# proj_arhipov_mcu.net
KiCad netlist of a schematic drawn in Altium Designer
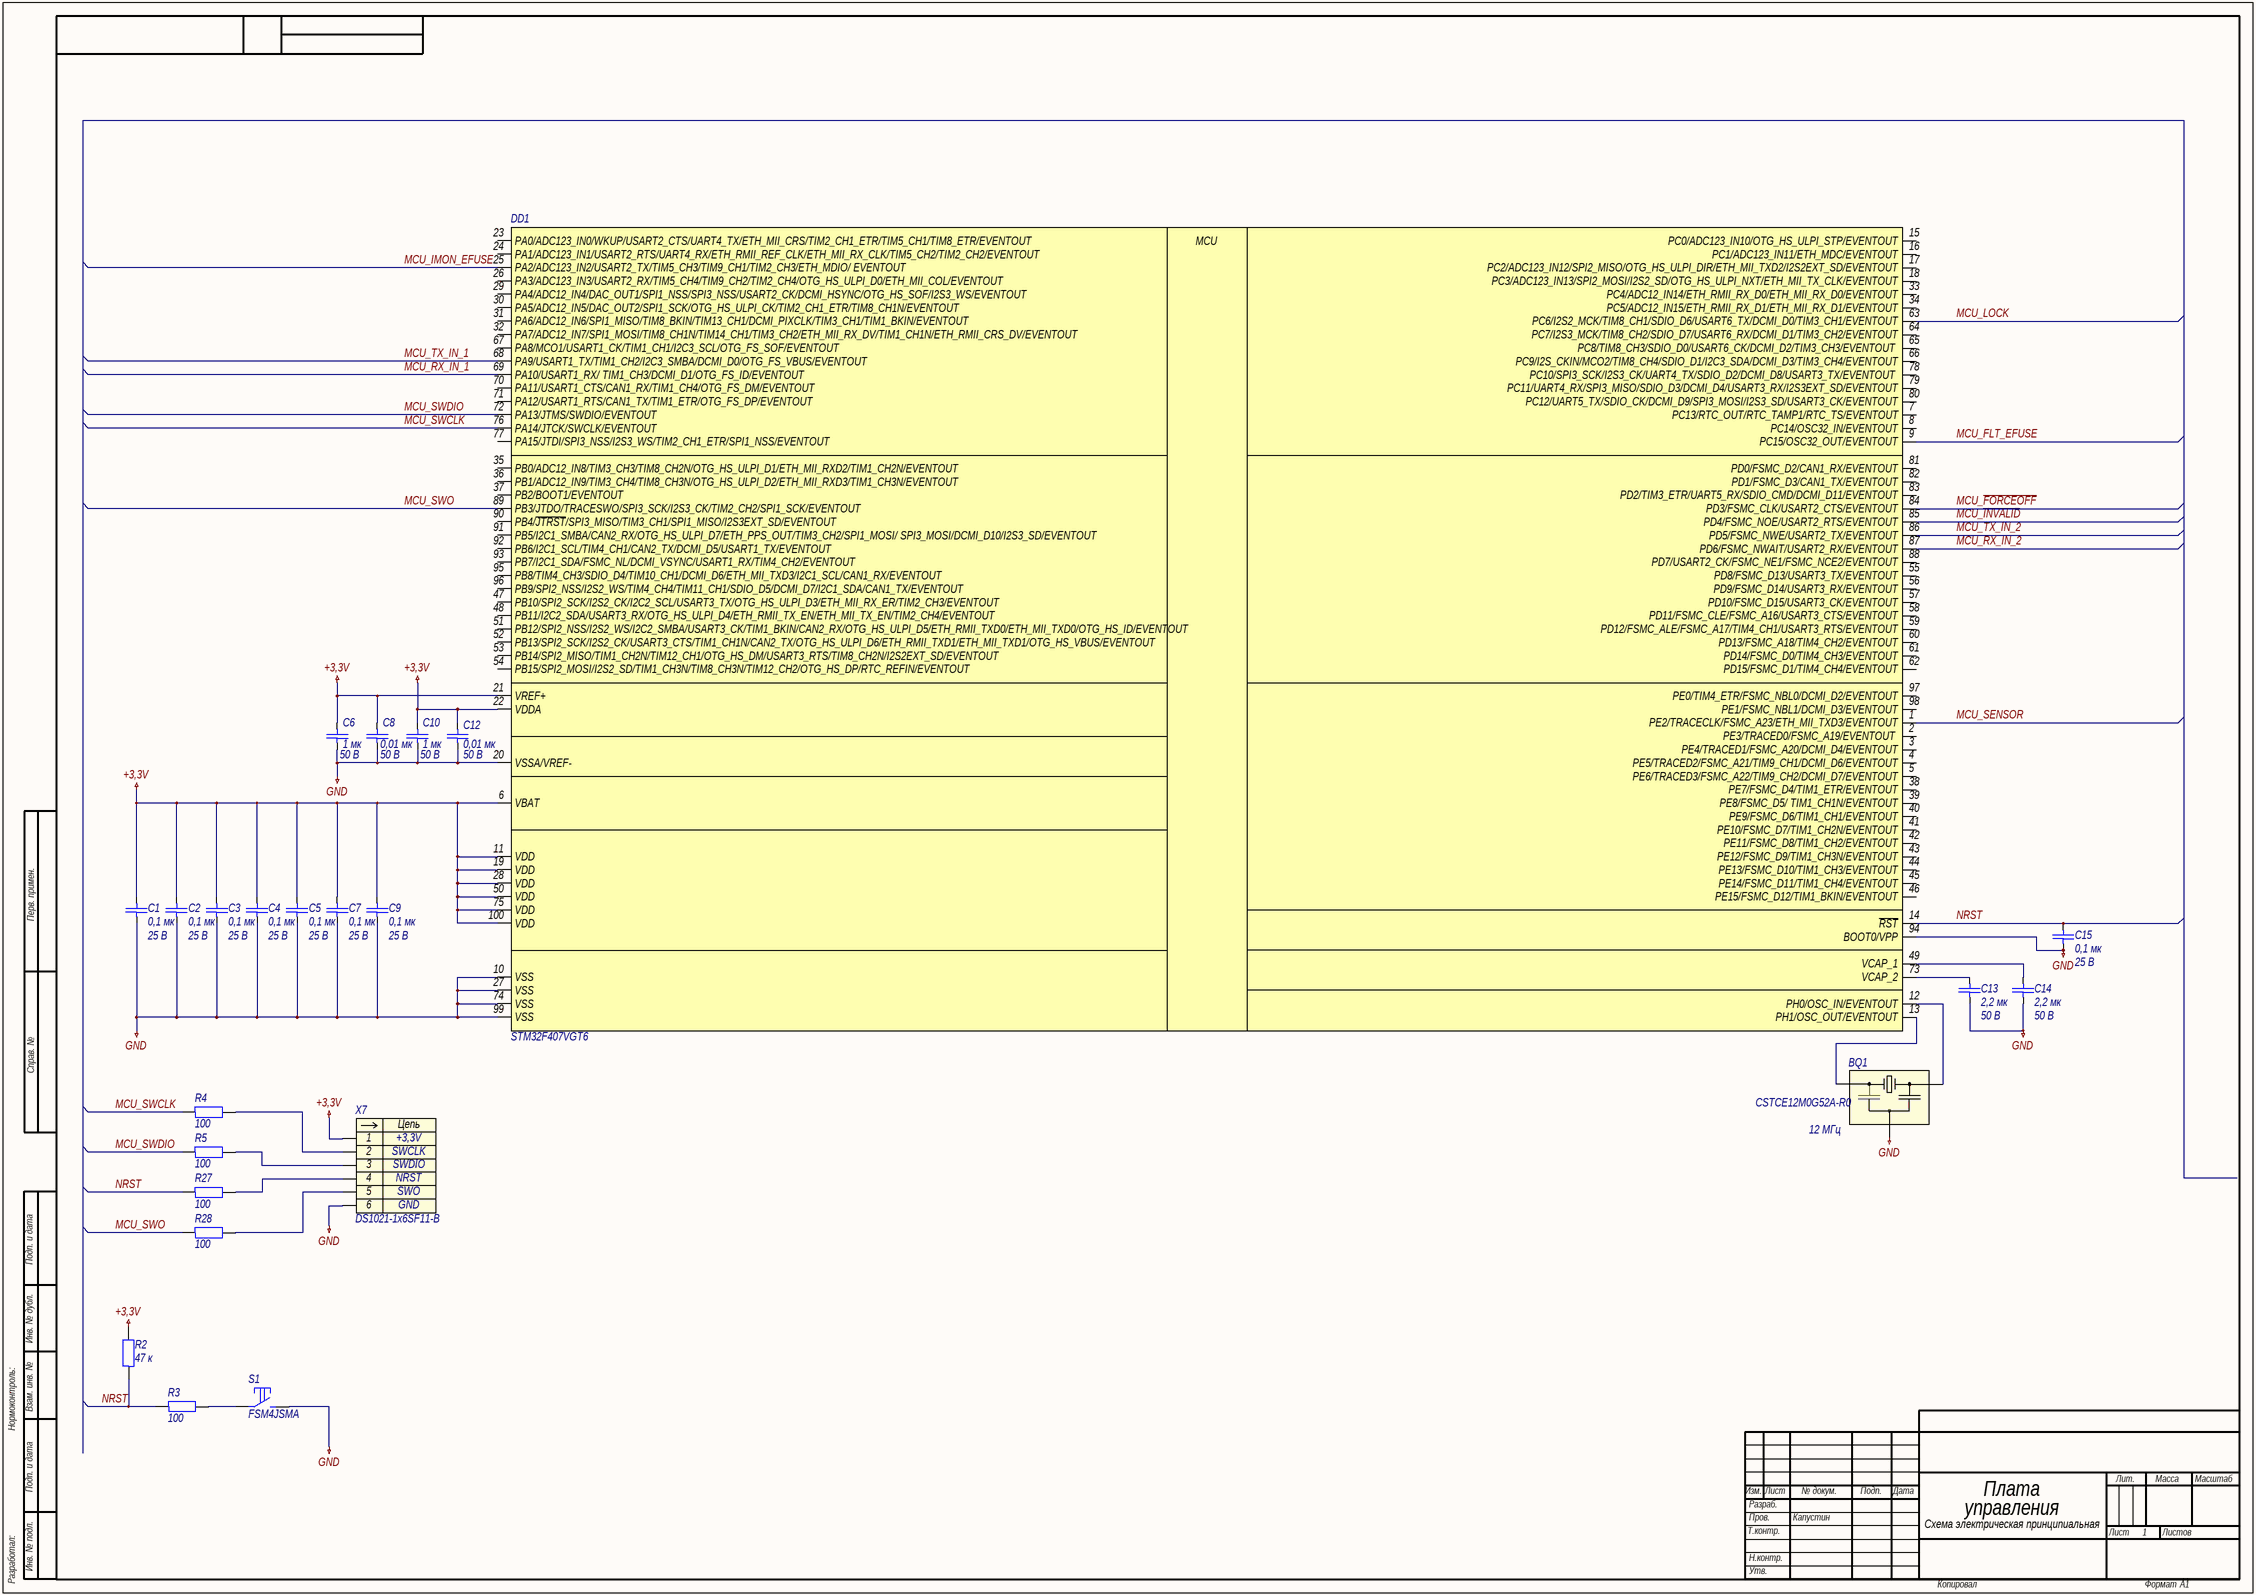
[diagram p0: proj_arhipov_mcu.SchDoc]

(export (version "E")
  (design (tool "Eeschema 10.0.6"))
  (components
    (comp (ref "BQ1")
      (value "CSTCE12M0G52A-R0")
      (footprint "CSTCE-3-320X130X70")
      (description "=Описание")
      (fields (field (name "ЧАСТОТA") "12 МГц"))
      (libsource (lib "Database_Students") (part "CSTCE12M0G52A-R0"))
    )
    (comp (ref "C1")
      (value "0,1 мк")
      (footprint "C0603")
      (description "=Описание")
      (fields (field (name "НАПРЯЖЕНИЕ") "25 В"))
      (libsource (lib "Database_Students") (part "CAPACITOR-NONPOLAR"))
    )
    (comp (ref "C2")
      (value "0,1 мк")
      (footprint "C0603")
      (description "=Описание")
      (fields (field (name "НАПРЯЖЕНИЕ") "25 В"))
      (libsource (lib "Database_Students") (part "CAPACITOR-NONPOLAR"))
    )
    (comp (ref "C3")
      (value "0,1 мк")
      (footprint "C0603")
      (description "=Описание")
      (fields (field (name "НАПРЯЖЕНИЕ") "25 В"))
      (libsource (lib "Database_Students") (part "CAPACITOR-NONPOLAR"))
    )
    (comp (ref "C4")
      (value "0,1 мк")
      (footprint "C0603")
      (description "=Описание")
      (fields (field (name "НАПРЯЖЕНИЕ") "25 В"))
      (libsource (lib "Database_Students") (part "CAPACITOR-NONPOLAR"))
    )
    (comp (ref "C5")
      (value "0,1 мк")
      (footprint "C0603")
      (description "=Описание")
      (fields (field (name "НАПРЯЖЕНИЕ") "25 В"))
      (libsource (lib "Database_Students") (part "CAPACITOR-NONPOLAR"))
    )
    (comp (ref "C6")
      (value "1 мк")
      (footprint "C0603")
      (description "=Описание")
      (fields (field (name "НАПРЯЖЕНИЕ") "50 В"))
      (libsource (lib "Database_Students") (part "CAPACITOR-NONPOLAR"))
    )
    (comp (ref "C7")
      (value "0,1 мк")
      (footprint "C0603")
      (description "=Описание")
      (fields (field (name "НАПРЯЖЕНИЕ") "25 В"))
      (libsource (lib "Database_Students") (part "CAPACITOR-NONPOLAR"))
    )
    (comp (ref "C8")
      (value "0,01 мк")
      (footprint "C0603")
      (description "=Описание")
      (fields (field (name "НАПРЯЖЕНИЕ") "50 В"))
      (libsource (lib "Database_Students") (part "CAPACITOR-NONPOLAR"))
    )
    (comp (ref "C9")
      (value "0,1 мк")
      (footprint "C0603")
      (description "=Описание")
      (fields (field (name "НАПРЯЖЕНИЕ") "25 В"))
      (libsource (lib "Database_Students") (part "CAPACITOR-NONPOLAR"))
    )
    (comp (ref "C10")
      (value "1 мк")
      (footprint "C0603")
      (description "=Описание")
      (fields (field (name "НАПРЯЖЕНИЕ") "50 В"))
      (libsource (lib "Database_Students") (part "CAPACITOR-NONPOLAR"))
    )
    (comp (ref "C12")
      (value "0,01 мк")
      (footprint "C0603")
      (description "=Описание")
      (fields (field (name "НАПРЯЖЕНИЕ") "50 В"))
      (libsource (lib "Database_Students") (part "CAPACITOR-NONPOLAR"))
    )
    (comp (ref "C13")
      (value "2,2 мк")
      (footprint "C0603")
      (description "=Описание")
      (fields (field (name "НАПРЯЖЕНИЕ") "50 В"))
      (libsource (lib "Database_Students") (part "CAPACITOR-NONPOLAR"))
    )
    (comp (ref "C14")
      (value "2,2 мк")
      (footprint "C0603")
      (description "=Описание")
      (fields (field (name "НАПРЯЖЕНИЕ") "50 В"))
      (libsource (lib "Database_Students") (part "CAPACITOR-NONPOLAR"))
    )
    (comp (ref "C15")
      (value "0,1 мк")
      (footprint "C0603")
      (description "=Описание")
      (fields (field (name "НАПРЯЖЕНИЕ") "25 В"))
      (libsource (lib "Database_Students") (part "CAPACITOR-NONPOLAR"))
    )
    (comp (ref "DD1")
      (value "STM32F407VGT6")
      (footprint "LQFP-100-P50-1400X1400X160-L60X22")
      (description "=Описание")
      (libsource (lib "Database_Students") (part "STM32F407VGT6"))
    )
    (comp (ref "R2")
      (value "47 к")
      (footprint "R0603")
      (description "=Описание")
      (libsource (lib "Database_Students") (part "RESISTOR-COMMON"))
    )
    (comp (ref "R3")
      (value "100")
      (footprint "R0603")
      (description "=Описание")
      (libsource (lib "Database_Students") (part "RESISTOR-COMMON"))
    )
    (comp (ref "R4")
      (value "100")
      (footprint "R0603")
      (description "=Описание")
      (libsource (lib "Database_Students") (part "RESISTOR-COMMON"))
    )
    (comp (ref "R5")
      (value "100")
      (footprint "R0603")
      (description "=Описание")
      (libsource (lib "Database_Students") (part "RESISTOR-COMMON"))
    )
    (comp (ref "R27")
      (value "100")
      (footprint "R0603")
      (description "=Описание")
      (libsource (lib "Database_Students") (part "RESISTOR-COMMON"))
    )
    (comp (ref "R28")
      (value "100")
      (footprint "R0603")
      (description "=Описание")
      (libsource (lib "Database_Students") (part "RESISTOR-COMMON"))
    )
    (comp (ref "S1")
      (value "FSM4JSMA")
      (footprint "FSM4JSMA")
      (description "=Описание")
      (libsource (lib "Database_Students") (part "BUTTON"))
    )
    (comp (ref "X7")
      (value "DS1021-1x6SF11-B")
      (footprint "DS1021-1X6SF11-B")
      (description "=Описание")
      (libsource (lib "Database_Students") (part "HEADER-6-PLG"))
    )
  )
  (nets
    (net (code "1") (name "+3,3V") (class "Default")
      (node (ref "C1") (pin "1") (pinfunction "1_1") (pintype "passive"))
      (node (ref "C10") (pin "1") (pinfunction "1_1") (pintype "passive"))
      (node (ref "C12") (pin "1") (pinfunction "1_1") (pintype "passive"))
      (node (ref "C2") (pin "1") (pinfunction "1_1") (pintype "passive"))
      (node (ref "C3") (pin "1") (pinfunction "1_1") (pintype "passive"))
      (node (ref "C4") (pin "1") (pinfunction "1_1") (pintype "passive"))
      (node (ref "C5") (pin "1") (pinfunction "1_1") (pintype "passive"))
      (node (ref "C6") (pin "1") (pinfunction "1_1") (pintype "passive"))
      (node (ref "C7") (pin "1") (pinfunction "1_1") (pintype "passive"))
      (node (ref "C8") (pin "1") (pinfunction "1_1") (pintype "passive"))
      (node (ref "C9") (pin "1") (pinfunction "1_1") (pintype "passive"))
      (node (ref "DD1") (pin "100") (pinfunction "VDD_100") (pintype "passive"))
      (node (ref "DD1") (pin "11") (pinfunction "VDD_11") (pintype "passive"))
      (node (ref "DD1") (pin "19") (pinfunction "VDD_19") (pintype "passive"))
      (node (ref "DD1") (pin "21") (pinfunction "VREF+_21") (pintype "passive"))
      (node (ref "DD1") (pin "22") (pinfunction "VDDA_22") (pintype "passive"))
      (node (ref "DD1") (pin "28") (pinfunction "VDD_28") (pintype "passive"))
      (node (ref "DD1") (pin "50") (pinfunction "VDD_50") (pintype "passive"))
      (node (ref "DD1") (pin "6") (pinfunction "VBAT_6") (pintype "passive"))
      (node (ref "DD1") (pin "75") (pinfunction "VDD_75") (pintype "passive"))
      (node (ref "R2") (pin "2") (pinfunction "2_2") (pintype "passive"))
      (node (ref "X7") (pin "1") (pinfunction "1_1") (pintype "passive"))
    )
    (net (code "2") (name "/MCU_FLT_EFUSE") (class "Default")
      (node (ref "DD1") (pin "9") (pinfunction "PC15/OSC32_OUT/EVENTOUT_9") (pintype "passive"))
    )
    (net (code "3") (name "/MCU_IMON_EFUSE") (class "Default")
      (node (ref "DD1") (pin "25") (pinfunction "PA2/ADC123_IN2/USART2_TX/TIM5_CH3/TIM9_CH1/TIM2_CH3/ETH_MDIO/_EVENTOUT_25") (pintype "passive"))
    )
    (net (code "4") (name "/MCU_LOCK") (class "Default")
      (node (ref "DD1") (pin "63") (pinfunction "PC6/I2S2_MCK/TIM8_CH1/SDIO_D6/USART6_TX/DCMI_D0/TIM3_CH1/EVENTOUT_63") (pintype "passive"))
    )
    (net (code "5") (name "/MCU_RX_IN_1") (class "Default")
      (node (ref "DD1") (pin "69") (pinfunction "PA10/USART1_RX/_TIM1_CH3/DCMI_D1/OTG_FS_ID/EVENTOUT_69") (pintype "passive"))
    )
    (net (code "6") (name "/MCU_RX_IN_2") (class "Default")
      (node (ref "DD1") (pin "87") (pinfunction "PD6/FSMC_NWAIT/USART2_RX/EVENTOUT_87") (pintype "passive"))
    )
    (net (code "7") (name "/MCU_SENSOR") (class "Default")
      (node (ref "DD1") (pin "1") (pinfunction "PE2/TRACECLK/FSMC_A23/ETH_MII_TXD3/EVENTOUT_1") (pintype "passive"))
    )
    (net (code "8") (name "/MCU_SWCLK") (class "Default")
      (node (ref "DD1") (pin "76") (pinfunction "PA14/JTCK/SWCLK/EVENTOUT_76") (pintype "passive"))
      (node (ref "R4") (pin "1") (pinfunction "1_1") (pintype "passive"))
    )
    (net (code "9") (name "/MCU_SWDIO") (class "Default")
      (node (ref "DD1") (pin "72") (pinfunction "PA13/JTMS/SWDIO/EVENTOUT_72") (pintype "passive"))
      (node (ref "R5") (pin "1") (pinfunction "1_1") (pintype "passive"))
    )
    (net (code "10") (name "/MCU_SWO") (class "Default")
      (node (ref "DD1") (pin "89") (pinfunction "PB3/JTDO/TRACESWO/SPI3_SCK/I2S3_CK/TIM2_CH2/SPI1_SCK/EVENTOUT_89") (pintype "passive"))
      (node (ref "R28") (pin "1") (pinfunction "1_1") (pintype "passive"))
    )
    (net (code "11") (name "/MCU_TX_IN_1") (class "Default")
      (node (ref "DD1") (pin "68") (pinfunction "PA9/USART1_TX/TIM1_CH2/I2C3_SMBA/DCMI_D0/OTG_FS_VBUS/EVENTOUT_68") (pintype "passive"))
    )
    (net (code "12") (name "/MCU_TX_IN_2") (class "Default")
      (node (ref "DD1") (pin "86") (pinfunction "PD5/FSMC_NWE/USART2_TX/EVENTOUT_86") (pintype "passive"))
    )
    (net (code "13") (name "/MCU_~{FORCEOFF}") (class "Default")
      (node (ref "DD1") (pin "84") (pinfunction "PD3/FSMC_CLK/USART2_CTS/EVENTOUT_84") (pintype "passive"))
    )
    (net (code "14") (name "/MCU_~{INVALID}") (class "Default")
      (node (ref "DD1") (pin "85") (pinfunction "PD4/FSMC_NOE/USART2_RTS/EVENTOUT_85") (pintype "passive"))
    )
    (net (code "15") (name "/NRST") (class "Default")
      (node (ref "C15") (pin "1") (pinfunction "1_1") (pintype "passive"))
      (node (ref "DD1") (pin "14") (pinfunction "~{RST}_14") (pintype "passive"))
      (node (ref "R2") (pin "1") (pinfunction "1_1") (pintype "passive"))
      (node (ref "R27") (pin "1") (pinfunction "1_1") (pintype "passive"))
      (node (ref "R3") (pin "1") (pinfunction "1_1") (pintype "passive"))
    )
    (net (code "16") (name "GND") (class "Default")
      (node (ref "BQ1") (pin "2") (pinfunction "2_2") (pintype "passive"))
      (node (ref "C1") (pin "2") (pinfunction "2_2") (pintype "passive"))
      (node (ref "C10") (pin "2") (pinfunction "2_2") (pintype "passive"))
      (node (ref "C12") (pin "2") (pinfunction "2_2") (pintype "passive"))
      (node (ref "C13") (pin "2") (pinfunction "2_2") (pintype "passive"))
      (node (ref "C14") (pin "2") (pinfunction "2_2") (pintype "passive"))
      (node (ref "C15") (pin "2") (pinfunction "2_2") (pintype "passive"))
      (node (ref "C2") (pin "2") (pinfunction "2_2") (pintype "passive"))
      (node (ref "C3") (pin "2") (pinfunction "2_2") (pintype "passive"))
      (node (ref "C4") (pin "2") (pinfunction "2_2") (pintype "passive"))
      (node (ref "C5") (pin "2") (pinfunction "2_2") (pintype "passive"))
      (node (ref "C6") (pin "2") (pinfunction "2_2") (pintype "passive"))
      (node (ref "C7") (pin "2") (pinfunction "2_2") (pintype "passive"))
      (node (ref "C8") (pin "2") (pinfunction "2_2") (pintype "passive"))
      (node (ref "C9") (pin "2") (pinfunction "2_2") (pintype "passive"))
      (node (ref "DD1") (pin "10") (pinfunction "VSS_10") (pintype "passive"))
      (node (ref "DD1") (pin "20") (pinfunction "VSSA/VREF-_20") (pintype "passive"))
      (node (ref "DD1") (pin "27") (pinfunction "VSS_27") (pintype "passive"))
      (node (ref "DD1") (pin "74") (pinfunction "VSS_74") (pintype "passive"))
      (node (ref "DD1") (pin "94") (pinfunction "BOOT0/VPP_94") (pintype "passive"))
      (node (ref "DD1") (pin "99") (pinfunction "VSS_99") (pintype "passive"))
      (node (ref "S1") (pin "2") (pinfunction "2_2") (pintype "passive"))
      (node (ref "X7") (pin "6") (pinfunction "6_6") (pintype "passive"))
    )
    (net (code "17") (name "Net-(DD1-PH0{slash}OSC_IN{slash}EVENTOUT)") (class "Default")
      (node (ref "BQ1") (pin "1") (pinfunction "1_1") (pintype "passive"))
      (node (ref "DD1") (pin "12") (pinfunction "PH0/OSC_IN/EVENTOUT_12") (pintype "passive"))
    )
    (net (code "18") (name "Net-(DD1-PH1{slash}OSC_OUT{slash}EVENTOUT)") (class "Default")
      (node (ref "BQ1") (pin "3") (pinfunction "3_3") (pintype "passive"))
      (node (ref "DD1") (pin "13") (pinfunction "PH1/OSC_OUT/EVENTOUT_13") (pintype "passive"))
    )
    (net (code "19") (name "Net-(DD1-VCAP_1)") (class "Default")
      (node (ref "C14") (pin "1") (pinfunction "1_1") (pintype "passive"))
      (node (ref "DD1") (pin "49") (pinfunction "VCAP_1_49") (pintype "passive"))
    )
    (net (code "20") (name "Net-(DD1-VCAP_2)") (class "Default")
      (node (ref "C13") (pin "1") (pinfunction "1_1") (pintype "passive"))
      (node (ref "DD1") (pin "73") (pinfunction "VCAP_2_73") (pintype "passive"))
    )
    (net (code "21") (name "Net-(R3-Pad2)") (class "Default")
      (node (ref "R3") (pin "2") (pinfunction "2_2") (pintype "passive"))
      (node (ref "S1") (pin "1") (pinfunction "1_1") (pintype "passive"))
    )
    (net (code "22") (name "Net-(R4-Pad2)") (class "Default")
      (node (ref "R4") (pin "2") (pinfunction "2_2") (pintype "passive"))
      (node (ref "X7") (pin "2") (pinfunction "2_2") (pintype "passive"))
    )
    (net (code "23") (name "Net-(R5-Pad2)") (class "Default")
      (node (ref "R5") (pin "2") (pinfunction "2_2") (pintype "passive"))
      (node (ref "X7") (pin "3") (pinfunction "3_3") (pintype "passive"))
    )
    (net (code "24") (name "Net-(R27-Pad2)") (class "Default")
      (node (ref "R27") (pin "2") (pinfunction "2_2") (pintype "passive"))
      (node (ref "X7") (pin "4") (pinfunction "4_4") (pintype "passive"))
    )
    (net (code "25") (name "Net-(R28-Pad2)") (class "Default")
      (node (ref "R28") (pin "2") (pinfunction "2_2") (pintype "passive"))
      (node (ref "X7") (pin "5") (pinfunction "5_5") (pintype "passive"))
    )
    (net (code "26") (name "unconnected-(DD1-PA0{slash}ADC123_IN0{slash}WKUP{slash}USART2_CTS{slash}UART4_TX{slash}ETH_MII_CRS{slash}TIM2_CH1_ETR{slash}TIM5_CH1{slash}TIM8_ETR{slash}EVENTOUT-Pad23)") (class "Default")
      (node (ref "DD1") (pin "23") (pinfunction "PA0/ADC123_IN0/WKUP/USART2_CTS/UART4_TX/ETH_MII_CRS/TIM2_CH1_ETR/TIM5_CH1/TIM8_ETR/EVENTOUT_23") (pintype "passive"))
    )
    (net (code "27") (name "unconnected-(DD1-PA1{slash}ADC123_IN1{slash}USART2_RTS{slash}UART4_RX{slash}ETH_RMII_REF_CLK{slash}ETH_MII_RX_CLK{slash}TIM5_CH2{slash}TIM2_CH2{slash}EVENTOUT-Pad24)") (class "Default")
      (node (ref "DD1") (pin "24") (pinfunction "PA1/ADC123_IN1/USART2_RTS/UART4_RX/ETH_RMII_REF_CLK/ETH_MII_RX_CLK/TIM5_CH2/TIM2_CH2/EVENTOUT_24") (pintype "passive"))
    )
    (net (code "28") (name "unconnected-(DD1-PA3{slash}ADC123_IN3{slash}USART2_RX{slash}TIM5_CH4{slash}TIM9_CH2{slash}TIM2_CH4{slash}OTG_HS_ULPI_D0{slash}ETH_MII_COL{slash}EVENTOUT-Pad26)") (class "Default")
      (node (ref "DD1") (pin "26") (pinfunction "PA3/ADC123_IN3/USART2_RX/TIM5_CH4/TIM9_CH2/TIM2_CH4/OTG_HS_ULPI_D0/ETH_MII_COL/EVENTOUT_26") (pintype "passive"))
    )
    (net (code "29") (name "unconnected-(DD1-PA4{slash}ADC12_IN4{slash}DAC_OUT1{slash}SPI1_NSS{slash}SPI3_NSS{slash}USART2_CK{slash}DCMI_HSYNC{slash}OTG_HS_SOF{slash}I2S3_WS{slash}EVENTOUT-Pad29)") (class "Default")
      (node (ref "DD1") (pin "29") (pinfunction "PA4/ADC12_IN4/DAC_OUT1/SPI1_NSS/SPI3_NSS/USART2_CK/DCMI_HSYNC/OTG_HS_SOF/I2S3_WS/EVENTOUT_29") (pintype "passive"))
    )
    (net (code "30") (name "unconnected-(DD1-PA5{slash}ADC12_IN5{slash}DAC_OUT2{slash}SPI1_SCK{slash}OTG_HS_ULPI_CK{slash}TIM2_CH1_ETR{slash}TIM8_CH1N{slash}EVENTOUT-Pad30)") (class "Default")
      (node (ref "DD1") (pin "30") (pinfunction "PA5/ADC12_IN5/DAC_OUT2/SPI1_SCK/OTG_HS_ULPI_CK/TIM2_CH1_ETR/TIM8_CH1N/EVENTOUT_30") (pintype "passive"))
    )
    (net (code "31") (name "unconnected-(DD1-PA6{slash}ADC12_IN6{slash}SPI1_MISO{slash}TIM8_BKIN{slash}TIM13_CH1{slash}DCMI_PIXCLK{slash}TIM3_CH1{slash}TIM1_BKIN{slash}EVENTOUT-Pad31)") (class "Default")
      (node (ref "DD1") (pin "31") (pinfunction "PA6/ADC12_IN6/SPI1_MISO/TIM8_BKIN/TIM13_CH1/DCMI_PIXCLK/TIM3_CH1/TIM1_BKIN/EVENTOUT_31") (pintype "passive"))
    )
    (net (code "32") (name "unconnected-(DD1-PA7{slash}ADC12_IN7{slash}SPI1_MOSI{slash}TIM8_CH1N{slash}TIM14_CH1{slash}TIM3_CH2{slash}ETH_MII_RX_DV{slash}TIM1_CH1N{slash}ETH_RMII_CRS_DV{slash}EVENTOUT-Pad32)") (class "Default")
      (node (ref "DD1") (pin "32") (pinfunction "PA7/ADC12_IN7/SPI1_MOSI/TIM8_CH1N/TIM14_CH1/TIM3_CH2/ETH_MII_RX_DV/TIM1_CH1N/ETH_RMII_CRS_DV/EVENTOUT_32") (pintype "passive"))
    )
    (net (code "33") (name "unconnected-(DD1-PA8{slash}MCO1{slash}USART1_CK{slash}TIM1_CH1{slash}I2C3_SCL{slash}OTG_FS_SOF{slash}EVENTOUT-Pad67)") (class "Default")
      (node (ref "DD1") (pin "67") (pinfunction "PA8/MCO1/USART1_CK/TIM1_CH1/I2C3_SCL/OTG_FS_SOF/EVENTOUT_67") (pintype "passive"))
    )
    (net (code "34") (name "unconnected-(DD1-PA11{slash}USART1_CTS{slash}CAN1_RX{slash}TIM1_CH4{slash}OTG_FS_DM{slash}EVENTOUT-Pad70)") (class "Default")
      (node (ref "DD1") (pin "70") (pinfunction "PA11/USART1_CTS/CAN1_RX/TIM1_CH4/OTG_FS_DM/EVENTOUT_70") (pintype "passive"))
    )
    (net (code "35") (name "unconnected-(DD1-PA12{slash}USART1_RTS{slash}CAN1_TX{slash}TIM1_ETR{slash}OTG_FS_DP{slash}EVENTOUT-Pad71)") (class "Default")
      (node (ref "DD1") (pin "71") (pinfunction "PA12/USART1_RTS/CAN1_TX/TIM1_ETR/OTG_FS_DP/EVENTOUT_71") (pintype "passive"))
    )
    (net (code "36") (name "unconnected-(DD1-PA15{slash}JTDI{slash}SPI3_NSS{slash}I2S3_WS{slash}TIM2_CH1_ETR{slash}SPI1_NSS{slash}EVENTOUT-Pad77)") (class "Default")
      (node (ref "DD1") (pin "77") (pinfunction "PA15/JTDI/SPI3_NSS/I2S3_WS/TIM2_CH1_ETR/SPI1_NSS/EVENTOUT_77") (pintype "passive"))
    )
    (net (code "37") (name "unconnected-(DD1-PB0{slash}ADC12_IN8{slash}TIM3_CH3{slash}TIM8_CH2N{slash}OTG_HS_ULPI_D1{slash}ETH_MII_RXD2{slash}TIM1_CH2N{slash}EVENTOUT-Pad35)") (class "Default")
      (node (ref "DD1") (pin "35") (pinfunction "PB0/ADC12_IN8/TIM3_CH3/TIM8_CH2N/OTG_HS_ULPI_D1/ETH_MII_RXD2/TIM1_CH2N/EVENTOUT_35") (pintype "passive"))
    )
    (net (code "38") (name "unconnected-(DD1-PB1{slash}ADC12_IN9{slash}TIM3_CH4{slash}TIM8_CH3N{slash}OTG_HS_ULPI_D2{slash}ETH_MII_RXD3{slash}TIM1_CH3N{slash}EVENTOUT-Pad36)") (class "Default")
      (node (ref "DD1") (pin "36") (pinfunction "PB1/ADC12_IN9/TIM3_CH4/TIM8_CH3N/OTG_HS_ULPI_D2/ETH_MII_RXD3/TIM1_CH3N/EVENTOUT_36") (pintype "passive"))
    )
    (net (code "39") (name "unconnected-(DD1-PB2{slash}BOOT1{slash}EVENTOUT-Pad37)") (class "Default")
      (node (ref "DD1") (pin "37") (pinfunction "PB2/BOOT1/EVENTOUT_37") (pintype "passive"))
    )
    (net (code "40") (name "unconnected-(DD1-PB4{slash}~{JTRST}{slash}SPI3_MISO{slash}TIM3_CH1{slash}SPI1_MISO{slash}I2S3EXT_SD{slash}EVENTOUT-Pad90)") (class "Default")
      (node (ref "DD1") (pin "90") (pinfunction "PB4/~{JTRST}/SPI3_MISO/TIM3_CH1/SPI1_MISO/I2S3EXT_SD/EVENTOUT_90") (pintype "passive"))
    )
    (net (code "41") (name "unconnected-(DD1-PB5{slash}I2C1_SMBA{slash}CAN2_RX{slash}OTG_HS_ULPI_D7{slash}ETH_PPS_OUT{slash}TIM3_CH2{slash}SPI1_MOSI{slash}_SPI3_MOSI{slash}DCMI_D10{slash}I2S3_SD{slash}EVENTOUT-Pad91)") (class "Default")
      (node (ref "DD1") (pin "91") (pinfunction "PB5/I2C1_SMBA/CAN2_RX/OTG_HS_ULPI_D7/ETH_PPS_OUT/TIM3_CH2/SPI1_MOSI/_SPI3_MOSI/DCMI_D10/I2S3_SD/EVENTOUT_91") (pintype "passive"))
    )
    (net (code "42") (name "unconnected-(DD1-PB6{slash}I2C1_SCL{slash}TIM4_CH1{slash}CAN2_TX{slash}DCMI_D5{slash}USART1_TX{slash}EVENTOUT-Pad92)") (class "Default")
      (node (ref "DD1") (pin "92") (pinfunction "PB6/I2C1_SCL/TIM4_CH1/CAN2_TX/DCMI_D5/USART1_TX/EVENTOUT_92") (pintype "passive"))
    )
    (net (code "43") (name "unconnected-(DD1-PB7{slash}I2C1_SDA{slash}FSMC_NL{slash}DCMI_VSYNC{slash}USART1_RX{slash}TIM4_CH2{slash}EVENTOUT-Pad93)") (class "Default")
      (node (ref "DD1") (pin "93") (pinfunction "PB7/I2C1_SDA/FSMC_NL/DCMI_VSYNC/USART1_RX/TIM4_CH2/EVENTOUT_93") (pintype "passive"))
    )
    (net (code "44") (name "unconnected-(DD1-PB8{slash}TIM4_CH3{slash}SDIO_D4{slash}TIM10_CH1{slash}DCMI_D6{slash}ETH_MII_TXD3{slash}I2C1_SCL{slash}CAN1_RX{slash}EVENTOUT-Pad95)") (class "Default")
      (node (ref "DD1") (pin "95") (pinfunction "PB8/TIM4_CH3/SDIO_D4/TIM10_CH1/DCMI_D6/ETH_MII_TXD3/I2C1_SCL/CAN1_RX/EVENTOUT_95") (pintype "passive"))
    )
    (net (code "45") (name "unconnected-(DD1-PB9{slash}SPI2_NSS{slash}I2S2_WS{slash}TIM4_CH4{slash}TIM11_CH1{slash}SDIO_D5{slash}DCMI_D7{slash}I2C1_SDA{slash}CAN1_TX{slash}EVENTOUT-Pad96)") (class "Default")
      (node (ref "DD1") (pin "96") (pinfunction "PB9/SPI2_NSS/I2S2_WS/TIM4_CH4/TIM11_CH1/SDIO_D5/DCMI_D7/I2C1_SDA/CAN1_TX/EVENTOUT_96") (pintype "passive"))
    )
    (net (code "46") (name "unconnected-(DD1-PB10{slash}SPI2_SCK{slash}I2S2_CK{slash}I2C2_SCL{slash}USART3_TX{slash}OTG_HS_ULPI_D3{slash}ETH_MII_RX_ER{slash}TIM2_CH3{slash}EVENTOUT-Pad47)") (class "Default")
      (node (ref "DD1") (pin "47") (pinfunction "PB10/SPI2_SCK/I2S2_CK/I2C2_SCL/USART3_TX/OTG_HS_ULPI_D3/ETH_MII_RX_ER/TIM2_CH3/EVENTOUT_47") (pintype "passive"))
    )
    (net (code "47") (name "unconnected-(DD1-PB11{slash}I2C2_SDA{slash}USART3_RX{slash}OTG_HS_ULPI_D4{slash}ETH_RMII_TX_EN{slash}ETH_MII_TX_EN{slash}TIM2_CH4{slash}EVENTOUT-Pad48)") (class "Default")
      (node (ref "DD1") (pin "48") (pinfunction "PB11/I2C2_SDA/USART3_RX/OTG_HS_ULPI_D4/ETH_RMII_TX_EN/ETH_MII_TX_EN/TIM2_CH4/EVENTOUT_48") (pintype "passive"))
    )
    (net (code "48") (name "unconnected-(DD1-PB12{slash}SPI2_NSS{slash}I2S2_WS{slash}I2C2_SMBA{slash}USART3_CK{slash}TIM1_BKIN{slash}CAN2_RX{slash}OTG_HS_ULPI_D5{slash}ETH_RMII_TXD0{slash}ETH_MII_TXD0{slash}OTG_HS_ID{slash}EVENTOUT-Pad51)") (class "Default")
      (node (ref "DD1") (pin "51") (pinfunction "PB12/SPI2_NSS/I2S2_WS/I2C2_SMBA/USART3_CK/TIM1_BKIN/CAN2_RX/OTG_HS_ULPI_D5/ETH_RMII_TXD0/ETH_MII_TXD0/OTG_HS_ID/EVENTOUT_51") (pintype "passive"))
    )
    (net (code "49") (name "unconnected-(DD1-PB13{slash}SPI2_SCK{slash}I2S2_CK{slash}USART3_CTS{slash}TIM1_CH1N{slash}CAN2_TX{slash}OTG_HS_ULPI_D6{slash}ETH_RMII_TXD1{slash}ETH_MII_TXD1{slash}OTG_HS_VBUS{slash}EVENTOUT-Pad52)") (class "Default")
      (node (ref "DD1") (pin "52") (pinfunction "PB13/SPI2_SCK/I2S2_CK/USART3_CTS/TIM1_CH1N/CAN2_TX/OTG_HS_ULPI_D6/ETH_RMII_TXD1/ETH_MII_TXD1/OTG_HS_VBUS/EVENTOUT_52") (pintype "passive"))
    )
    (net (code "50") (name "unconnected-(DD1-PB14{slash}SPI2_MISO{slash}TIM1_CH2N{slash}TIM12_CH1{slash}OTG_HS_DM{slash}USART3_RTS{slash}TIM8_CH2N{slash}I2S2EXT_SD{slash}EVENTOUT-Pad53)") (class "Default")
      (node (ref "DD1") (pin "53") (pinfunction "PB14/SPI2_MISO/TIM1_CH2N/TIM12_CH1/OTG_HS_DM/USART3_RTS/TIM8_CH2N/I2S2EXT_SD/EVENTOUT_53") (pintype "passive"))
    )
    (net (code "51") (name "unconnected-(DD1-PB15{slash}SPI2_MOSI{slash}I2S2_SD{slash}TIM1_CH3N{slash}TIM8_CH3N{slash}TIM12_CH2{slash}OTG_HS_DP{slash}RTC_REFIN{slash}EVENTOUT-Pad54)") (class "Default")
      (node (ref "DD1") (pin "54") (pinfunction "PB15/SPI2_MOSI/I2S2_SD/TIM1_CH3N/TIM8_CH3N/TIM12_CH2/OTG_HS_DP/RTC_REFIN/EVENTOUT_54") (pintype "passive"))
    )
    (net (code "52") (name "unconnected-(DD1-PC0{slash}ADC123_IN10{slash}OTG_HS_ULPI_STP{slash}EVENTOUT-Pad15)") (class "Default")
      (node (ref "DD1") (pin "15") (pinfunction "PC0/ADC123_IN10/OTG_HS_ULPI_STP/EVENTOUT_15") (pintype "passive"))
    )
    (net (code "53") (name "unconnected-(DD1-PC1{slash}ADC123_IN11{slash}ETH_MDC{slash}EVENTOUT-Pad16)") (class "Default")
      (node (ref "DD1") (pin "16") (pinfunction "PC1/ADC123_IN11/ETH_MDC/EVENTOUT_16") (pintype "passive"))
    )
    (net (code "54") (name "unconnected-(DD1-PC2{slash}ADC123_IN12{slash}SPI2_MISO{slash}OTG_HS_ULPI_DIR{slash}ETH_MII_TXD2{slash}I2S2EXT_SD{slash}EVENTOUT-Pad17)") (class "Default")
      (node (ref "DD1") (pin "17") (pinfunction "PC2/ADC123_IN12/SPI2_MISO/OTG_HS_ULPI_DIR/ETH_MII_TXD2/I2S2EXT_SD/EVENTOUT_17") (pintype "passive"))
    )
    (net (code "55") (name "unconnected-(DD1-PC3{slash}ADC123_IN13{slash}SPI2_MOSI{slash}I2S2_SD{slash}OTG_HS_ULPI_NXT{slash}ETH_MII_TX_CLK{slash}EVENTOUT-Pad18)") (class "Default")
      (node (ref "DD1") (pin "18") (pinfunction "PC3/ADC123_IN13/SPI2_MOSI/I2S2_SD/OTG_HS_ULPI_NXT/ETH_MII_TX_CLK/EVENTOUT_18") (pintype "passive"))
    )
    (net (code "56") (name "unconnected-(DD1-PC4{slash}ADC12_IN14{slash}ETH_RMII_RX_D0{slash}ETH_MII_RX_D0{slash}EVENTOUT-Pad33)") (class "Default")
      (node (ref "DD1") (pin "33") (pinfunction "PC4/ADC12_IN14/ETH_RMII_RX_D0/ETH_MII_RX_D0/EVENTOUT_33") (pintype "passive"))
    )
    (net (code "57") (name "unconnected-(DD1-PC5{slash}ADC12_IN15{slash}ETH_RMII_RX_D1{slash}ETH_MII_RX_D1{slash}EVENTOUT-Pad34)") (class "Default")
      (node (ref "DD1") (pin "34") (pinfunction "PC5/ADC12_IN15/ETH_RMII_RX_D1/ETH_MII_RX_D1/EVENTOUT_34") (pintype "passive"))
    )
    (net (code "58") (name "unconnected-(DD1-PC7{slash}I2S3_MCK{slash}TIM8_CH2{slash}SDIO_D7{slash}USART6_RX{slash}DCMI_D1{slash}TIM3_CH2{slash}EVENTOUT-Pad64)") (class "Default")
      (node (ref "DD1") (pin "64") (pinfunction "PC7/I2S3_MCK/TIM8_CH2/SDIO_D7/USART6_RX/DCMI_D1/TIM3_CH2/EVENTOUT_64") (pintype "passive"))
    )
    (net (code "59") (name "unconnected-(DD1-PC8{slash}TIM8_CH3{slash}SDIO_D0{slash}USART6_CK{slash}DCMI_D2{slash}TIM3_CH3{slash}EVENTOUT-Pad65)") (class "Default")
      (node (ref "DD1") (pin "65") (pinfunction "PC8/TIM8_CH3/SDIO_D0/USART6_CK/DCMI_D2/TIM3_CH3/EVENTOUT_65") (pintype "passive"))
    )
    (net (code "60") (name "unconnected-(DD1-PC9{slash}I2S_CKIN{slash}MCO2{slash}TIM8_CH4{slash}SDIO_D1{slash}I2C3_SDA{slash}DCMI_D3{slash}TIM3_CH4{slash}EVENTOUT-Pad66)") (class "Default")
      (node (ref "DD1") (pin "66") (pinfunction "PC9/I2S_CKIN/MCO2/TIM8_CH4/SDIO_D1/I2C3_SDA/DCMI_D3/TIM3_CH4/EVENTOUT_66") (pintype "passive"))
    )
    (net (code "61") (name "unconnected-(DD1-PC10{slash}SPI3_SCK{slash}I2S3_CK{slash}UART4_TX{slash}SDIO_D2{slash}DCMI_D8{slash}USART3_TX{slash}EVENTOUT-Pad78)") (class "Default")
      (node (ref "DD1") (pin "78") (pinfunction "PC10/SPI3_SCK/I2S3_CK/UART4_TX/SDIO_D2/DCMI_D8/USART3_TX/EVENTOUT_78") (pintype "passive"))
    )
    (net (code "62") (name "unconnected-(DD1-PC11{slash}UART4_RX{slash}SPI3_MISO{slash}SDIO_D3{slash}DCMI_D4{slash}USART3_RX{slash}I2S3EXT_SD{slash}EVENTOUT-Pad79)") (class "Default")
      (node (ref "DD1") (pin "79") (pinfunction "PC11/UART4_RX/SPI3_MISO/SDIO_D3/DCMI_D4/USART3_RX/I2S3EXT_SD/EVENTOUT_79") (pintype "passive"))
    )
    (net (code "63") (name "unconnected-(DD1-PC12{slash}UART5_TX{slash}SDIO_CK{slash}DCMI_D9{slash}SPI3_MOSI{slash}I2S3_SD{slash}USART3_CK{slash}EVENTOUT-Pad80)") (class "Default")
      (node (ref "DD1") (pin "80") (pinfunction "PC12/UART5_TX/SDIO_CK/DCMI_D9/SPI3_MOSI/I2S3_SD/USART3_CK/EVENTOUT_80") (pintype "passive"))
    )
    (net (code "64") (name "unconnected-(DD1-PC13{slash}RTC_OUT{slash}RTC_TAMP1{slash}RTC_TS{slash}EVENTOUT-Pad7)") (class "Default")
      (node (ref "DD1") (pin "7") (pinfunction "PC13/RTC_OUT/RTC_TAMP1/RTC_TS/EVENTOUT_7") (pintype "passive"))
    )
    (net (code "65") (name "unconnected-(DD1-PC14{slash}OSC32_IN{slash}EVENTOUT-Pad8)") (class "Default")
      (node (ref "DD1") (pin "8") (pinfunction "PC14/OSC32_IN/EVENTOUT_8") (pintype "passive"))
    )
    (net (code "66") (name "unconnected-(DD1-PD0{slash}FSMC_D2{slash}CAN1_RX{slash}EVENTOUT-Pad81)") (class "Default")
      (node (ref "DD1") (pin "81") (pinfunction "PD0/FSMC_D2/CAN1_RX/EVENTOUT_81") (pintype "passive"))
    )
    (net (code "67") (name "unconnected-(DD1-PD1{slash}FSMC_D3{slash}CAN1_TX{slash}EVENTOUT-Pad82)") (class "Default")
      (node (ref "DD1") (pin "82") (pinfunction "PD1/FSMC_D3/CAN1_TX/EVENTOUT_82") (pintype "passive"))
    )
    (net (code "68") (name "unconnected-(DD1-PD2{slash}TIM3_ETR{slash}UART5_RX{slash}SDIO_CMD{slash}DCMI_D11{slash}EVENTOUT-Pad83)") (class "Default")
      (node (ref "DD1") (pin "83") (pinfunction "PD2/TIM3_ETR/UART5_RX/SDIO_CMD/DCMI_D11/EVENTOUT_83") (pintype "passive"))
    )
    (net (code "69") (name "unconnected-(DD1-PD7{slash}USART2_CK{slash}FSMC_NE1{slash}FSMC_NCE2{slash}EVENTOUT-Pad88)") (class "Default")
      (node (ref "DD1") (pin "88") (pinfunction "PD7/USART2_CK/FSMC_NE1/FSMC_NCE2/EVENTOUT_88") (pintype "passive"))
    )
    (net (code "70") (name "unconnected-(DD1-PD8{slash}FSMC_D13{slash}USART3_TX{slash}EVENTOUT-Pad55)") (class "Default")
      (node (ref "DD1") (pin "55") (pinfunction "PD8/FSMC_D13/USART3_TX/EVENTOUT_55") (pintype "passive"))
    )
    (net (code "71") (name "unconnected-(DD1-PD9{slash}FSMC_D14{slash}USART3_RX{slash}EVENTOUT-Pad56)") (class "Default")
      (node (ref "DD1") (pin "56") (pinfunction "PD9/FSMC_D14/USART3_RX/EVENTOUT_56") (pintype "passive"))
    )
    (net (code "72") (name "unconnected-(DD1-PD10{slash}FSMC_D15{slash}USART3_CK{slash}EVENTOUT-Pad57)") (class "Default")
      (node (ref "DD1") (pin "57") (pinfunction "PD10/FSMC_D15/USART3_CK/EVENTOUT_57") (pintype "passive"))
    )
    (net (code "73") (name "unconnected-(DD1-PD11{slash}FSMC_CLE{slash}FSMC_A16{slash}USART3_CTS{slash}EVENTOUT-Pad58)") (class "Default")
      (node (ref "DD1") (pin "58") (pinfunction "PD11/FSMC_CLE/FSMC_A16/USART3_CTS/EVENTOUT_58") (pintype "passive"))
    )
    (net (code "74") (name "unconnected-(DD1-PD12{slash}FSMC_ALE{slash}FSMC_A17{slash}TIM4_CH1{slash}USART3_RTS{slash}EVENTOUT-Pad59)") (class "Default")
      (node (ref "DD1") (pin "59") (pinfunction "PD12/FSMC_ALE/FSMC_A17/TIM4_CH1/USART3_RTS/EVENTOUT_59") (pintype "passive"))
    )
    (net (code "75") (name "unconnected-(DD1-PD13{slash}FSMC_A18{slash}TIM4_CH2{slash}EVENTOUT-Pad60)") (class "Default")
      (node (ref "DD1") (pin "60") (pinfunction "PD13/FSMC_A18/TIM4_CH2/EVENTOUT_60") (pintype "passive"))
    )
    (net (code "76") (name "unconnected-(DD1-PD14{slash}FSMC_D0{slash}TIM4_CH3{slash}EVENTOUT-Pad61)") (class "Default")
      (node (ref "DD1") (pin "61") (pinfunction "PD14/FSMC_D0/TIM4_CH3/EVENTOUT_61") (pintype "passive"))
    )
    (net (code "77") (name "unconnected-(DD1-PD15{slash}FSMC_D1{slash}TIM4_CH4{slash}EVENTOUT-Pad62)") (class "Default")
      (node (ref "DD1") (pin "62") (pinfunction "PD15/FSMC_D1/TIM4_CH4/EVENTOUT_62") (pintype "passive"))
    )
    (net (code "78") (name "unconnected-(DD1-PE0{slash}TIM4_ETR{slash}FSMC_NBL0{slash}DCMI_D2{slash}EVENTOUT-Pad97)") (class "Default")
      (node (ref "DD1") (pin "97") (pinfunction "PE0/TIM4_ETR/FSMC_NBL0/DCMI_D2/EVENTOUT_97") (pintype "passive"))
    )
    (net (code "79") (name "unconnected-(DD1-PE1{slash}FSMC_NBL1{slash}DCMI_D3{slash}EVENTOUT-Pad98)") (class "Default")
      (node (ref "DD1") (pin "98") (pinfunction "PE1/FSMC_NBL1/DCMI_D3/EVENTOUT_98") (pintype "passive"))
    )
    (net (code "80") (name "unconnected-(DD1-PE3{slash}TRACED0{slash}FSMC_A19{slash}EVENTOUT-Pad2)") (class "Default")
      (node (ref "DD1") (pin "2") (pinfunction "PE3/TRACED0/FSMC_A19/EVENTOUT_2") (pintype "passive"))
    )
    (net (code "81") (name "unconnected-(DD1-PE4{slash}TRACED1{slash}FSMC_A20{slash}DCMI_D4{slash}EVENTOUT-Pad3)") (class "Default")
      (node (ref "DD1") (pin "3") (pinfunction "PE4/TRACED1/FSMC_A20/DCMI_D4/EVENTOUT_3") (pintype "passive"))
    )
    (net (code "82") (name "unconnected-(DD1-PE5{slash}TRACED2{slash}FSMC_A21{slash}TIM9_CH1{slash}DCMI_D6{slash}EVENTOUT-Pad4)") (class "Default")
      (node (ref "DD1") (pin "4") (pinfunction "PE5/TRACED2/FSMC_A21/TIM9_CH1/DCMI_D6/EVENTOUT_4") (pintype "passive"))
    )
    (net (code "83") (name "unconnected-(DD1-PE6{slash}TRACED3{slash}FSMC_A22{slash}TIM9_CH2{slash}DCMI_D7{slash}EVENTOUT-Pad5)") (class "Default")
      (node (ref "DD1") (pin "5") (pinfunction "PE6/TRACED3/FSMC_A22/TIM9_CH2/DCMI_D7/EVENTOUT_5") (pintype "passive"))
    )
    (net (code "84") (name "unconnected-(DD1-PE7{slash}FSMC_D4{slash}TIM1_ETR{slash}EVENTOUT-Pad38)") (class "Default")
      (node (ref "DD1") (pin "38") (pinfunction "PE7/FSMC_D4/TIM1_ETR/EVENTOUT_38") (pintype "passive"))
    )
    (net (code "85") (name "unconnected-(DD1-PE8{slash}FSMC_D5{slash}_TIM1_CH1N{slash}EVENTOUT-Pad39)") (class "Default")
      (node (ref "DD1") (pin "39") (pinfunction "PE8/FSMC_D5/_TIM1_CH1N/EVENTOUT_39") (pintype "passive"))
    )
    (net (code "86") (name "unconnected-(DD1-PE9{slash}FSMC_D6{slash}TIM1_CH1{slash}EVENTOUT-Pad40)") (class "Default")
      (node (ref "DD1") (pin "40") (pinfunction "PE9/FSMC_D6/TIM1_CH1/EVENTOUT_40") (pintype "passive"))
    )
    (net (code "87") (name "unconnected-(DD1-PE10{slash}FSMC_D7{slash}TIM1_CH2N{slash}EVENTOUT-Pad41)") (class "Default")
      (node (ref "DD1") (pin "41") (pinfunction "PE10/FSMC_D7/TIM1_CH2N/EVENTOUT_41") (pintype "passive"))
    )
    (net (code "88") (name "unconnected-(DD1-PE11{slash}FSMC_D8{slash}TIM1_CH2{slash}EVENTOUT-Pad42)") (class "Default")
      (node (ref "DD1") (pin "42") (pinfunction "PE11/FSMC_D8/TIM1_CH2/EVENTOUT_42") (pintype "passive"))
    )
    (net (code "89") (name "unconnected-(DD1-PE12{slash}FSMC_D9{slash}TIM1_CH3N{slash}EVENTOUT-Pad43)") (class "Default")
      (node (ref "DD1") (pin "43") (pinfunction "PE12/FSMC_D9/TIM1_CH3N/EVENTOUT_43") (pintype "passive"))
    )
    (net (code "90") (name "unconnected-(DD1-PE13{slash}FSMC_D10{slash}TIM1_CH3{slash}EVENTOUT-Pad44)") (class "Default")
      (node (ref "DD1") (pin "44") (pinfunction "PE13/FSMC_D10/TIM1_CH3/EVENTOUT_44") (pintype "passive"))
    )
    (net (code "91") (name "unconnected-(DD1-PE14{slash}FSMC_D11{slash}TIM1_CH4{slash}EVENTOUT-Pad45)") (class "Default")
      (node (ref "DD1") (pin "45") (pinfunction "PE14/FSMC_D11/TIM1_CH4/EVENTOUT_45") (pintype "passive"))
    )
    (net (code "92") (name "unconnected-(DD1-PE15{slash}FSMC_D12{slash}TIM1_BKIN{slash}EVENTOUT-Pad46)") (class "Default")
      (node (ref "DD1") (pin "46") (pinfunction "PE15/FSMC_D12/TIM1_BKIN/EVENTOUT_46") (pintype "passive"))
    )
  )
)
